# Main_Board_with_3_3v.net
KiCad netlist of a schematic drawn in EAGLE
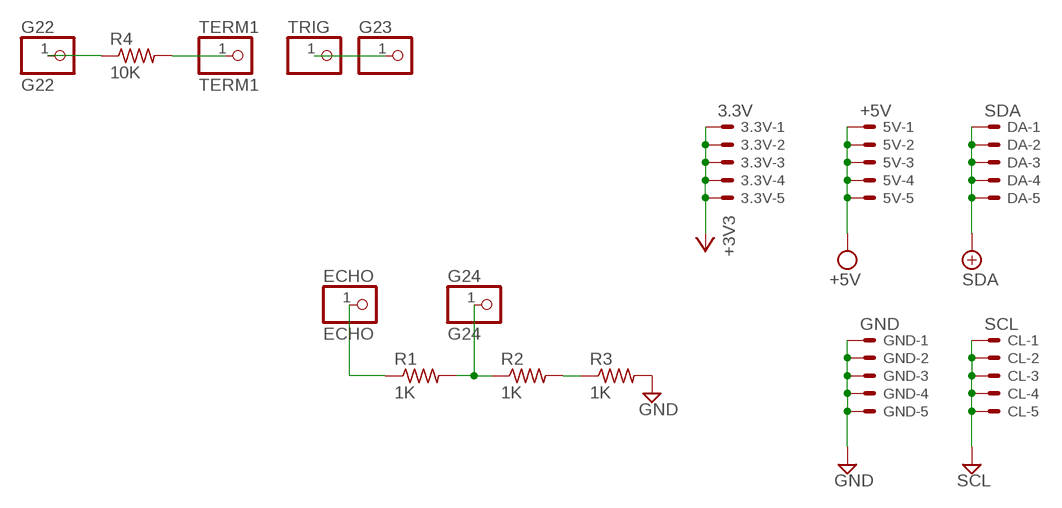
[diagram p0: schematic, sheet 1]

(export (version "E")
  (design (tool "Eeschema 10.0.6"))
  (components
    (comp (ref "3.3V")
      (value "3.3V")
      (footprint "eagle-import:22-23-2051")
      (fields (field (name "MF") "MOLEX") (field (name "MPN") "22-23-2051"))
      (libsource (lib "eagle-import") (part "22-23-2051"))
    )
    (comp (ref "5V")
      (value "+5V")
      (footprint "eagle-import:22-23-2051")
      (fields (field (name "MF") "MOLEX") (field (name "MPN") "22-23-2051"))
      (libsource (lib "eagle-import") (part "22-23-2051"))
    )
    (comp (ref "CL")
      (value "SCL")
      (footprint "eagle-import:22-23-2051")
      (fields (field (name "MF") "MOLEX") (field (name "MPN") "22-23-2051"))
      (libsource (lib "eagle-import") (part "22-23-2051"))
    )
    (comp (ref "DA")
      (value "SDA")
      (footprint "eagle-import:22-23-2051")
      (fields (field (name "MF") "MOLEX") (field (name "MPN") "22-23-2051"))
      (libsource (lib "eagle-import") (part "22-23-2051"))
    )
    (comp (ref "ECHO")
      (value "ECHO")
      (footprint "eagle-import:1X01")
      (libsource (lib "eagle-import") (part "PINHD-1X1"))
    )
    (comp (ref "G22")
      (value "G22")
      (footprint "eagle-import:1X01")
      (libsource (lib "eagle-import") (part "PINHD-1X1"))
    )
    (comp (ref "G23")
      (value "PINHD-1X1")
      (footprint "eagle-import:1X01")
      (libsource (lib "eagle-import") (part "PINHD-1X1"))
    )
    (comp (ref "G24")
      (value "G24")
      (footprint "eagle-import:1X01")
      (libsource (lib "eagle-import") (part "PINHD-1X1"))
    )
    (comp (ref "GND")
      (value "GND")
      (footprint "eagle-import:22-23-2051")
      (fields (field (name "MF") "MOLEX") (field (name "MPN") "22-23-2051"))
      (libsource (lib "eagle-import") (part "22-23-2051"))
    )
    (comp (ref "R1")
      (value "1K")
      (footprint "eagle-import:0204_7")
      (libsource (lib "eagle-import") (part "R-US_0204/7"))
    )
    (comp (ref "R2")
      (value "1K")
      (footprint "eagle-import:0204_7")
      (libsource (lib "eagle-import") (part "R-US_0204/7"))
    )
    (comp (ref "R3")
      (value "1K")
      (footprint "eagle-import:0204_7")
      (libsource (lib "eagle-import") (part "R-US_0204/7"))
    )
    (comp (ref "R4")
      (value "10K")
      (footprint "eagle-import:0204_7")
      (libsource (lib "eagle-import") (part "R-US_0204/7"))
    )
    (comp (ref "TERM1")
      (value "TERM1")
      (footprint "eagle-import:1X01")
      (libsource (lib "eagle-import") (part "PINHD-1X1"))
    )
    (comp (ref "TRIG")
      (value "PINHD-1X1")
      (footprint "eagle-import:1X01")
      (libsource (lib "eagle-import") (part "PINHD-1X1"))
    )
  )
  (nets
    (net (code "1") (name "+3V3") (class "Default")
      (node (ref "3.3V") (pin "1") (pinfunction "S_1") (pintype "passive"))
      (node (ref "3.3V") (pin "2") (pinfunction "S_2") (pintype "passive"))
      (node (ref "3.3V") (pin "3") (pinfunction "S_3") (pintype "passive"))
      (node (ref "3.3V") (pin "4") (pinfunction "S_4") (pintype "passive"))
      (node (ref "3.3V") (pin "5") (pinfunction "S_5") (pintype "passive"))
    )
    (net (code "2") (name "+5V") (class "Default")
      (node (ref "5V") (pin "1") (pinfunction "S_1") (pintype "passive"))
      (node (ref "5V") (pin "2") (pinfunction "S_2") (pintype "passive"))
      (node (ref "5V") (pin "3") (pinfunction "S_3") (pintype "passive"))
      (node (ref "5V") (pin "4") (pinfunction "S_4") (pintype "passive"))
      (node (ref "5V") (pin "5") (pinfunction "S_5") (pintype "passive"))
    )
    (net (code "3") (name "GND") (class "Default")
      (node (ref "GND") (pin "1") (pinfunction "S_1") (pintype "passive"))
      (node (ref "GND") (pin "2") (pinfunction "S_2") (pintype "passive"))
      (node (ref "GND") (pin "3") (pinfunction "S_3") (pintype "passive"))
      (node (ref "GND") (pin "4") (pinfunction "S_4") (pintype "passive"))
      (node (ref "GND") (pin "5") (pinfunction "S_5") (pintype "passive"))
      (node (ref "R3") (pin "2") (pinfunction "2_2") (pintype "passive"))
    )
    (net (code "4") (name "Net-(ECHO-Pad1)") (class "Default")
      (node (ref "ECHO") (pin "1") (pinfunction "1_1") (pintype "passive"))
      (node (ref "R1") (pin "1") (pinfunction "1_1") (pintype "passive"))
    )
    (net (code "5") (name "Net-(G22-Pad1)") (class "Default")
      (node (ref "G22") (pin "1") (pinfunction "1_1") (pintype "passive"))
      (node (ref "R4") (pin "1") (pinfunction "1_1") (pintype "passive"))
    )
    (net (code "6") (name "Net-(G23-Pad1)") (class "Default")
      (node (ref "G23") (pin "1") (pinfunction "1_1") (pintype "passive"))
      (node (ref "TRIG") (pin "1") (pinfunction "1_1") (pintype "passive"))
    )
    (net (code "7") (name "Net-(G24-Pad1)") (class "Default")
      (node (ref "G24") (pin "1") (pinfunction "1_1") (pintype "passive"))
      (node (ref "R1") (pin "2") (pinfunction "2_2") (pintype "passive"))
      (node (ref "R2") (pin "1") (pinfunction "1_1") (pintype "passive"))
    )
    (net (code "8") (name "Net-(R2-Pad2)") (class "Default")
      (node (ref "R2") (pin "2") (pinfunction "2_2") (pintype "passive"))
      (node (ref "R3") (pin "1") (pinfunction "1_1") (pintype "passive"))
    )
    (net (code "9") (name "Net-(R4-Pad2)") (class "Default")
      (node (ref "R4") (pin "2") (pinfunction "2_2") (pintype "passive"))
      (node (ref "TERM1") (pin "1") (pinfunction "1_1") (pintype "passive"))
    )
    (net (code "10") (name "SCL") (class "Default")
      (node (ref "CL") (pin "1") (pinfunction "S_1") (pintype "passive"))
      (node (ref "CL") (pin "2") (pinfunction "S_2") (pintype "passive"))
      (node (ref "CL") (pin "3") (pinfunction "S_3") (pintype "passive"))
      (node (ref "CL") (pin "4") (pinfunction "S_4") (pintype "passive"))
      (node (ref "CL") (pin "5") (pinfunction "S_5") (pintype "passive"))
    )
    (net (code "11") (name "SDA") (class "Default")
      (node (ref "DA") (pin "1") (pinfunction "S_1") (pintype "passive"))
      (node (ref "DA") (pin "2") (pinfunction "S_2") (pintype "passive"))
      (node (ref "DA") (pin "3") (pinfunction "S_3") (pintype "passive"))
      (node (ref "DA") (pin "4") (pinfunction "S_4") (pintype "passive"))
      (node (ref "DA") (pin "5") (pinfunction "S_5") (pintype "passive"))
    )
  )
)
